# 801_GridPos8.net
KiCad netlist of a schematic drawn in Altium Designer
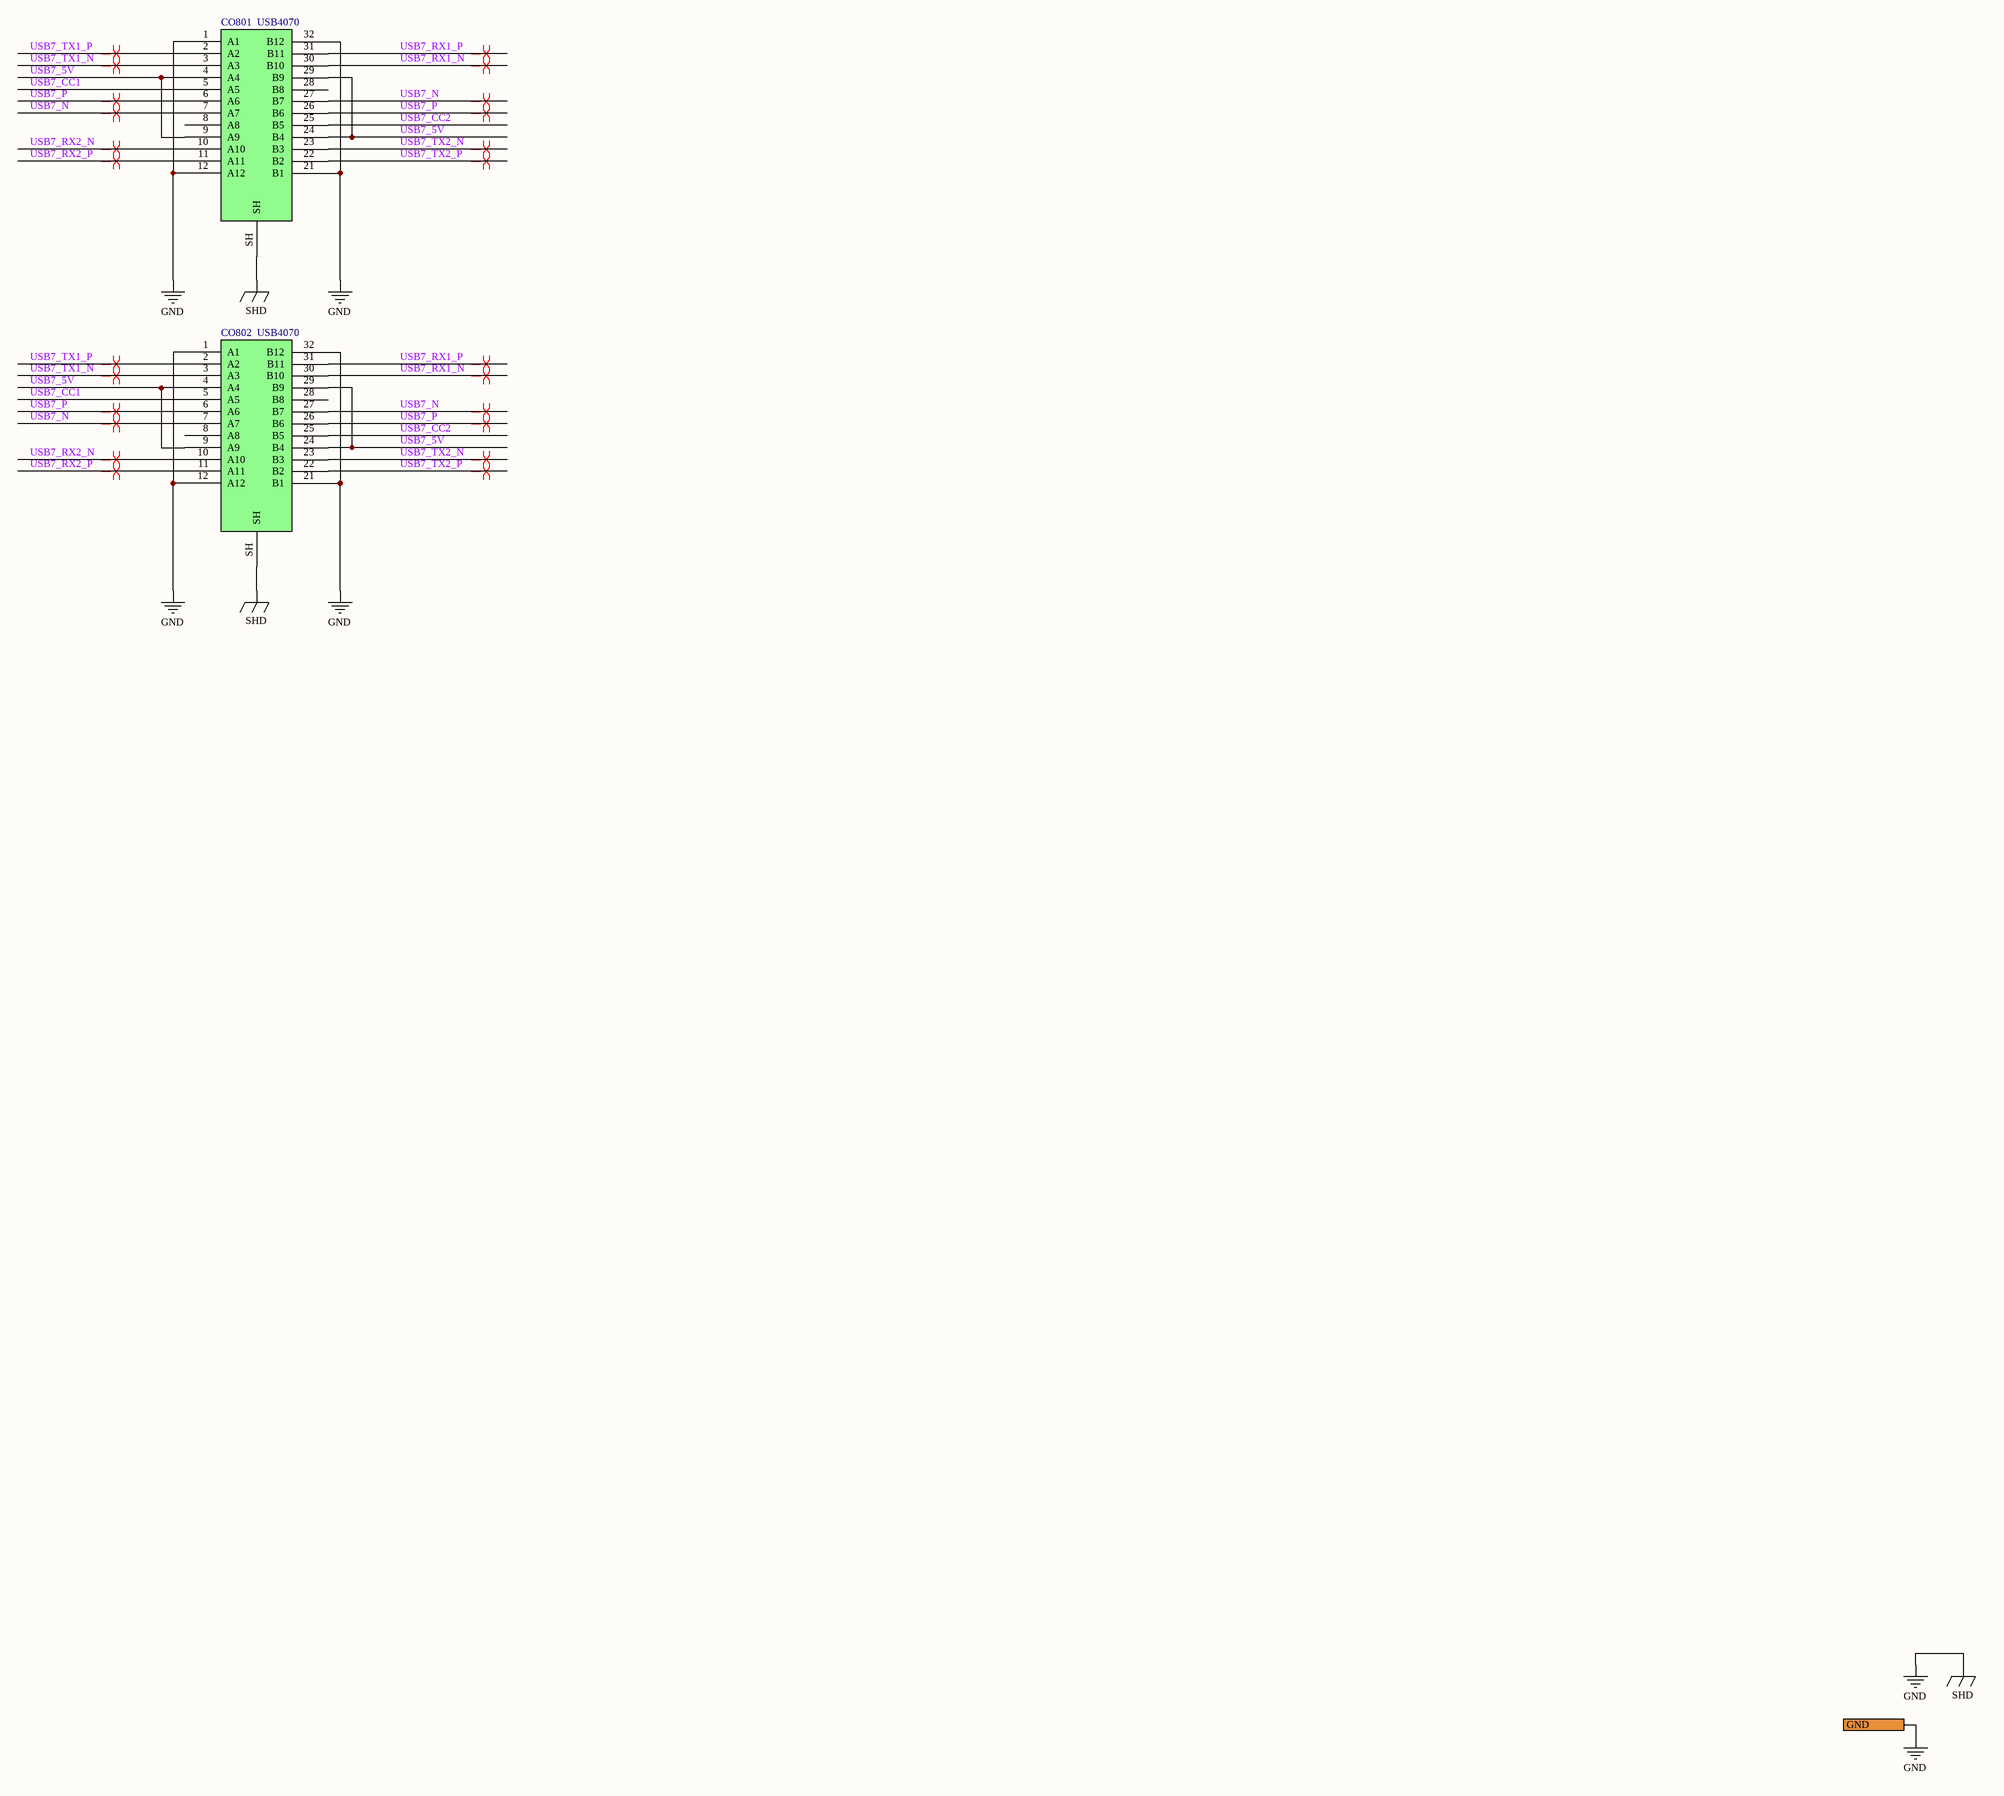
[diagram p0: 801_GridPos8.SchDoc]

(export (version "E")
  (design (tool "Eeschema 10.0.6"))
  (components
    (comp (ref "CO801")
      (value "USB4070")
      (footprint "USB4070-30-C")
      (description "USB4070-30-C")
      (fields (field (name "REFVAL") "USB4070") (field (name "PART NUMBER") "CO0021"))
      (libsource (lib "GTS_Database") (part "USB-CC"))
    )
    (comp (ref "CO802")
      (value "USB4070")
      (footprint "USB4070-30-C")
      (description "USB4070-30-C")
      (fields (field (name "REFVAL") "USB4070") (field (name "PART NUMBER") "CO0021"))
      (libsource (lib "GTS_Database") (part "USB-CC"))
    )
  )
  (nets
    (net (code "1") (name "/USB7_5V") (class "Default")
      (node (ref "CO801") (pin "24") (pinfunction "B4_24") (pintype "passive"))
      (node (ref "CO801") (pin "29") (pinfunction "B9_29") (pintype "passive"))
      (node (ref "CO801") (pin "4") (pinfunction "A4_4") (pintype "passive"))
      (node (ref "CO801") (pin "9") (pinfunction "A9_9") (pintype "passive"))
      (node (ref "CO802") (pin "24") (pinfunction "B4_24") (pintype "passive"))
      (node (ref "CO802") (pin "29") (pinfunction "B9_29") (pintype "passive"))
      (node (ref "CO802") (pin "4") (pinfunction "A4_4") (pintype "passive"))
      (node (ref "CO802") (pin "9") (pinfunction "A9_9") (pintype "passive"))
    )
    (net (code "2") (name "/USB7_CC1") (class "Default")
      (node (ref "CO801") (pin "5") (pinfunction "A5_5") (pintype "passive"))
      (node (ref "CO802") (pin "5") (pinfunction "A5_5") (pintype "passive"))
    )
    (net (code "3") (name "/USB7_CC2") (class "Default")
      (node (ref "CO801") (pin "25") (pinfunction "B5_25") (pintype "passive"))
      (node (ref "CO802") (pin "25") (pinfunction "B5_25") (pintype "passive"))
    )
    (net (code "4") (name "/USB7_N") (class "Default")
      (node (ref "CO801") (pin "27") (pinfunction "B7_27") (pintype "passive"))
      (node (ref "CO801") (pin "7") (pinfunction "A7_7") (pintype "passive"))
      (node (ref "CO802") (pin "27") (pinfunction "B7_27") (pintype "passive"))
      (node (ref "CO802") (pin "7") (pinfunction "A7_7") (pintype "passive"))
    )
    (net (code "5") (name "/USB7_P") (class "Default")
      (node (ref "CO801") (pin "26") (pinfunction "B6_26") (pintype "passive"))
      (node (ref "CO801") (pin "6") (pinfunction "A6_6") (pintype "passive"))
      (node (ref "CO802") (pin "26") (pinfunction "B6_26") (pintype "passive"))
      (node (ref "CO802") (pin "6") (pinfunction "A6_6") (pintype "passive"))
    )
    (net (code "6") (name "/USB7_RX1_N") (class "Default")
      (node (ref "CO801") (pin "30") (pinfunction "B10_30") (pintype "passive"))
      (node (ref "CO802") (pin "30") (pinfunction "B10_30") (pintype "passive"))
    )
    (net (code "7") (name "/USB7_RX1_P") (class "Default")
      (node (ref "CO801") (pin "31") (pinfunction "B11_31") (pintype "passive"))
      (node (ref "CO802") (pin "31") (pinfunction "B11_31") (pintype "passive"))
    )
    (net (code "8") (name "/USB7_RX2_N") (class "Default")
      (node (ref "CO801") (pin "10") (pinfunction "A10_10") (pintype "passive"))
      (node (ref "CO802") (pin "10") (pinfunction "A10_10") (pintype "passive"))
    )
    (net (code "9") (name "/USB7_RX2_P") (class "Default")
      (node (ref "CO801") (pin "11") (pinfunction "A11_11") (pintype "passive"))
      (node (ref "CO802") (pin "11") (pinfunction "A11_11") (pintype "passive"))
    )
    (net (code "10") (name "/USB7_TX1_N") (class "Default")
      (node (ref "CO801") (pin "3") (pinfunction "A3_3") (pintype "passive"))
      (node (ref "CO802") (pin "3") (pinfunction "A3_3") (pintype "passive"))
    )
    (net (code "11") (name "/USB7_TX1_P") (class "Default")
      (node (ref "CO801") (pin "2") (pinfunction "A2_2") (pintype "passive"))
      (node (ref "CO802") (pin "2") (pinfunction "A2_2") (pintype "passive"))
    )
    (net (code "12") (name "/USB7_TX2_N") (class "Default")
      (node (ref "CO801") (pin "23") (pinfunction "B3_23") (pintype "passive"))
      (node (ref "CO802") (pin "23") (pinfunction "B3_23") (pintype "passive"))
    )
    (net (code "13") (name "/USB7_TX2_P") (class "Default")
      (node (ref "CO801") (pin "22") (pinfunction "B2_22") (pintype "passive"))
      (node (ref "CO802") (pin "22") (pinfunction "B2_22") (pintype "passive"))
    )
    (net (code "14") (name "GND") (class "Default")
      (node (ref "CO801") (pin "1") (pinfunction "A1_1") (pintype "passive"))
      (node (ref "CO801") (pin "12") (pinfunction "A12_12") (pintype "passive"))
      (node (ref "CO801") (pin "21") (pinfunction "B1_21") (pintype "passive"))
      (node (ref "CO801") (pin "32") (pinfunction "B12_32") (pintype "passive"))
      (node (ref "CO801") (pin "SH") (pinfunction "SH_SH") (pintype "power_in"))
      (node (ref "CO802") (pin "1") (pinfunction "A1_1") (pintype "passive"))
      (node (ref "CO802") (pin "12") (pinfunction "A12_12") (pintype "passive"))
      (node (ref "CO802") (pin "21") (pinfunction "B1_21") (pintype "passive"))
      (node (ref "CO802") (pin "32") (pinfunction "B12_32") (pintype "passive"))
      (node (ref "CO802") (pin "SH") (pinfunction "SH_SH") (pintype "power_in"))
    )
    (net (code "15") (name "unconnected-(CO801-A8-Pad8)") (class "Default")
      (node (ref "CO801") (pin "8") (pinfunction "A8_8") (pintype "passive"))
    )
    (net (code "16") (name "unconnected-(CO801-B8-Pad28)") (class "Default")
      (node (ref "CO801") (pin "28") (pinfunction "B8_28") (pintype "passive"))
    )
    (net (code "17") (name "unconnected-(CO802-A8-Pad8)") (class "Default")
      (node (ref "CO802") (pin "8") (pinfunction "A8_8") (pintype "passive"))
    )
    (net (code "18") (name "unconnected-(CO802-B8-Pad28)") (class "Default")
      (node (ref "CO802") (pin "28") (pinfunction "B8_28") (pintype "passive"))
    )
  )
)
